# Sheet3.net
KiCad netlist of a schematic drawn in Altium Designer
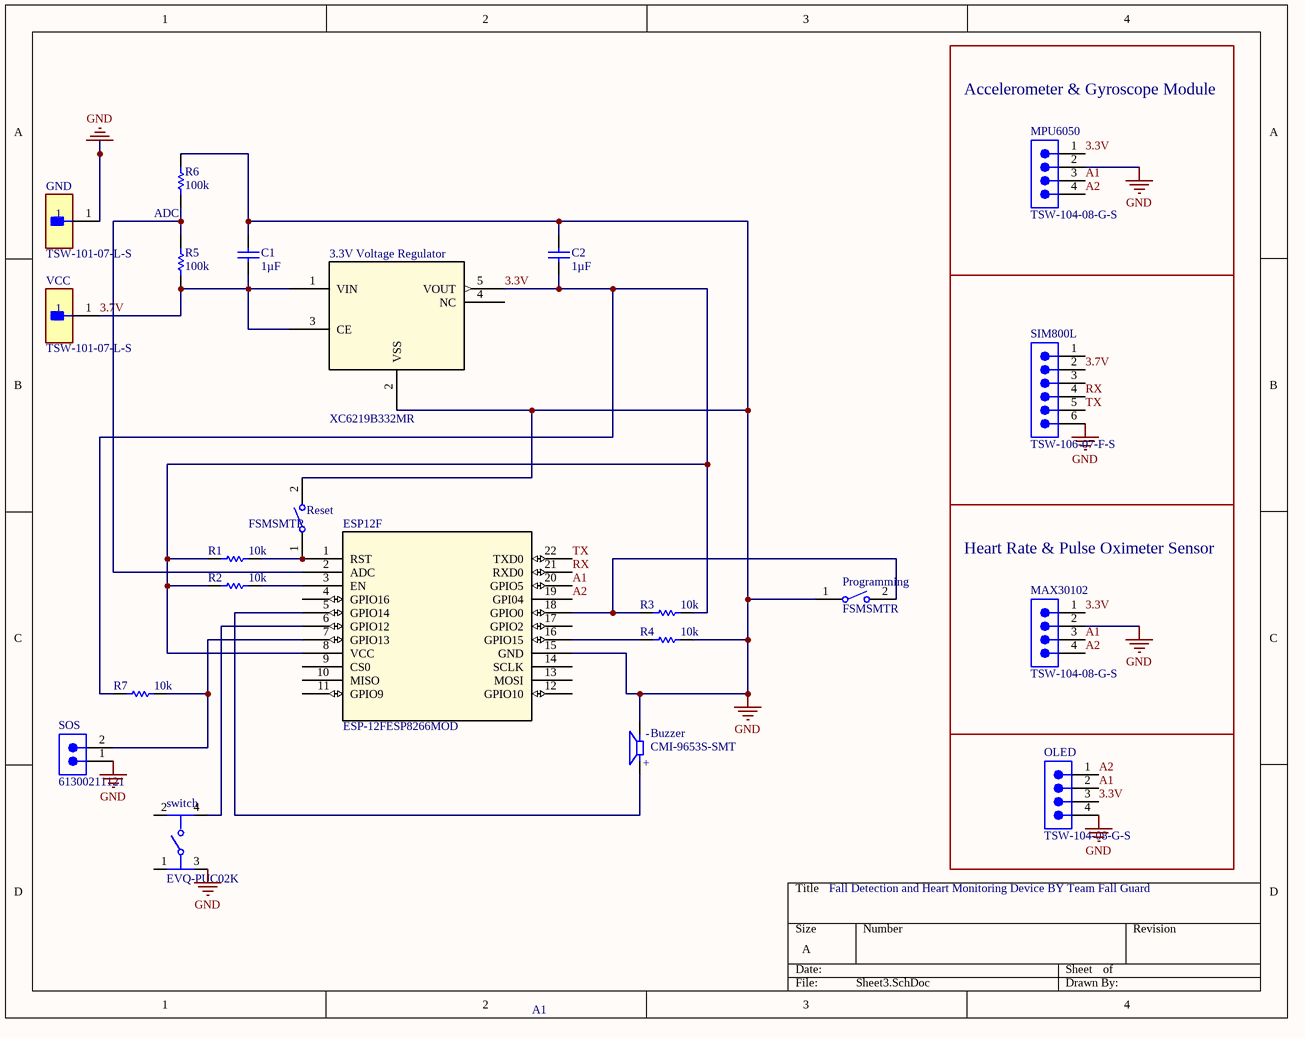
[diagram p0: Sheet3.SchDoc]

(export (version "E")
  (design (tool "Eeschema 10.0.6"))
  (components
    (comp (ref "3.3V Voltage Regulator")
      (value "XC6219B332MR")
      (footprint "SOT-25_TOR")
      (description "No Description Available")
      (libsource (lib "XC6219B332MR") (part "XC6219B332MR"))
    )
    (comp (ref "Buzzer")
      (value "CMI-9653S-SMT")
      (footprint "CUI_CMI-9653S-SMT")
      (fields (field (name "MF") "Same Sky") (field (name "MP") "CMI-9653S-SMT-TR"))
      (libsource (lib "CMI-9653S-SMT") (part "CMI-9653S-SMT"))
    )
    (comp (ref "C1")
      (value "1µF")
      (footprint "CAPC1608X90X35LL10T15")
      (description "Chip Capacitor, 1 uF, +/- 10%, 10 V, -55 to 85 degC, 0603 (1608 Metric), RoHS, Tape and Reel")
      (fields (field (name "MANUFACTURER") "Murata") (field (name "TOLERANCE") "10%"))
      (libsource (lib "Altium Content Vault") (part "CAP-NP-2"))
    )
    (comp (ref "C2")
      (value "1µF")
      (footprint "CAPC1608X90X35LL10T15")
      (description "Chip Capacitor, 1 uF, +/- 10%, 10 V, -55 to 85 degC, 0603 (1608 Metric), RoHS, Tape and Reel")
      (fields (field (name "MANUFACTURER") "Murata") (field (name "TOLERANCE") "10%"))
      (libsource (lib "Altium Content Vault") (part "CAP-NP-2"))
    )
    (comp (ref "ESP12F")
      (value "ESP-12FESP8266MOD")
      (footprint "ESP-12FESP8266MOD_AIT")
      (description "No Description Available")
      (libsource (lib "ESP-12FESP8266MOD") (part "ESP-12FESP8266MOD"))
    )
    (comp (ref "GND")
      (value "TSW-101-07-L-S")
      (footprint "FP-TSW-101-07-L-S-MFG")
      (description "CONN HEADER VERT 1POS")
      (libsource (lib "Altium Content Vault") (part "dd45045ce8184df9e99e12baf3f412c"))
    )
    (comp (ref "MAX30102")
      (value "TSW-104-08-G-S")
      (footprint "SMTC-TSW-104-08-X-S")
      (description "0.025\" SQ Post Header, Through-hole, Vertical, -55 to 125 degC, 2.54 mm Pitch, 4-Pin, Male, RoHS")
      (fields (field (name "MANUFACTURER") "Samtec"))
      (libsource (lib "Altium Content Vault") (part "SMTC-TSW-104-08-X-S"))
    )
    (comp (ref "MPU6050")
      (value "TSW-104-08-G-S")
      (footprint "SMTC-TSW-104-08-X-S")
      (description "0.025\" SQ Post Header, Through-hole, Vertical, -55 to 125 degC, 2.54 mm Pitch, 4-Pin, Male, RoHS")
      (fields (field (name "MANUFACTURER") "Samtec"))
      (libsource (lib "Altium Content Vault") (part "SMTC-TSW-104-08-X-S"))
    )
    (comp (ref "OLED")
      (value "TSW-104-08-G-S")
      (footprint "SMTC-TSW-104-08-X-S")
      (description "0.025\" SQ Post Header, Through-hole, Vertical, -55 to 125 degC, 2.54 mm Pitch, 4-Pin, Male, RoHS")
      (fields (field (name "MANUFACTURER") "Samtec"))
      (libsource (lib "Altium Content Vault") (part "SMTC-TSW-104-08-X-S"))
    )
    (comp (ref "Programming")
      (value "FSMSMTR")
      (footprint "TECO-FSMSMTR_V")
      (description "FSMSM Push Button Switch, 50 mA, -35 to 85 degC, 2-Pin SMD, RoHS, Tape and Reel")
      (fields (field (name "MANUFACTURER") "TE Connectivity"))
      (libsource (lib "Altium Content Vault") (part "SW-SPST-2_C"))
    )
    (comp (ref "R1")
      (value "10k")
      (footprint "RESC1609X50X30NL8T20")
      (description "Chip Resistor, 10 KOhm, +/- 1%, 100 mW, -55 to 155 degC, 0603 (1608 Metric), RoHS, Tape and Reel")
      (fields (field (name "MANUFACTURER") "Vishay Semiconductor"))
      (libsource (lib "Altium Content Vault") (part "RES-2"))
    )
    (comp (ref "R2")
      (value "10k")
      (footprint "RESC1609X50X30NL8T20")
      (description "Chip Resistor, 10 KOhm, +/- 1%, 100 mW, -55 to 155 degC, 0603 (1608 Metric), RoHS, Tape and Reel")
      (fields (field (name "MANUFACTURER") "Vishay Semiconductor"))
      (libsource (lib "Altium Content Vault") (part "RES-2"))
    )
    (comp (ref "R3")
      (value "10k")
      (footprint "RESC1609X50X30NL8T20")
      (description "Chip Resistor, 10 KOhm, +/- 1%, 100 mW, -55 to 155 degC, 0603 (1608 Metric), RoHS, Tape and Reel")
      (fields (field (name "MANUFACTURER") "Vishay Semiconductor"))
      (libsource (lib "Altium Content Vault") (part "RES-2"))
    )
    (comp (ref "R4")
      (value "10k")
      (footprint "RESC1609X50X30NL8T20")
      (description "Chip Resistor, 10 KOhm, +/- 1%, 100 mW, -55 to 155 degC, 0603 (1608 Metric), RoHS, Tape and Reel")
      (fields (field (name "MANUFACTURER") "Vishay Semiconductor"))
      (libsource (lib "Altium Content Vault") (part "RES-2"))
    )
    (comp (ref "R5")
      (value "100k")
      (footprint "RESC1609X50X30NL8T20")
      (description "Chip Resistor, 10 KOhm, +/- 1%, 100 mW, -55 to 155 degC, 0603 (1608 Metric), RoHS, Tape and Reel")
      (fields (field (name "MANUFACTURER") "Vishay Semiconductor"))
      (libsource (lib "Altium Content Vault") (part "RES-2"))
    )
    (comp (ref "R6")
      (value "100k")
      (footprint "RESC1609X50X30NL8T20")
      (description "Chip Resistor, 10 KOhm, +/- 1%, 100 mW, -55 to 155 degC, 0603 (1608 Metric), RoHS, Tape and Reel")
      (fields (field (name "MANUFACTURER") "Vishay Semiconductor"))
      (libsource (lib "Altium Content Vault") (part "RES-2"))
    )
    (comp (ref "R7")
      (value "10k")
      (footprint "RESC1609X50X30NL8T20")
      (description "Chip Resistor, 10 KOhm, +/- 1%, 100 mW, -55 to 155 degC, 0603 (1608 Metric), RoHS, Tape and Reel")
      (fields (field (name "MANUFACTURER") "Vishay Semiconductor"))
      (libsource (lib "Altium Content Vault") (part "RES-2"))
    )
    (comp (ref "Reset")
      (value "FSMSMTR")
      (footprint "TECO-FSMSMTR_V")
      (description "FSMSM Push Button Switch, 50 mA, -35 to 85 degC, 2-Pin SMD, RoHS, Tape and Reel")
      (fields (field (name "MANUFACTURER") "TE Connectivity"))
      (libsource (lib "Altium Content Vault") (part "SW-SPST-2_C"))
    )
    (comp (ref "SIM800L")
      (value "TSW-106-07-F-S")
      (footprint "SMTC-TSW-106-07-X-S")
      (description "0.025\" SQ Post Header, Through-hole, Vertical, -55 to 125 degC, 2.54 mm Pitch, 6-Pin, Male, RoHS")
      (fields (field (name "MANUFACTURER") "Samtec"))
      (libsource (lib "Altium Content Vault") (part "SMTC-TSW-106-X-X-S-X"))
    )
    (comp (ref "SOS")
      (value "61300211121")
      (footprint "61300211121")
      (libsource (lib "Altium Content Vault") (part "Header_Male_1R_02P"))
    )
    (comp (ref "switch")
      (value "EVQ-PUC02K")
      (footprint "FP-EVQ-PUC02K-MFG")
      (description "SWITCH TACTILE SPST-NO 0.05A 12V")
      (libsource (lib "Altium Content Vault") (part "cb67941ecbda1860b707deecc235d4d"))
    )
    (comp (ref "VCC")
      (value "TSW-101-07-L-S")
      (footprint "FP-TSW-101-07-L-S-MFG")
      (description "CONN HEADER VERT 1POS")
      (libsource (lib "Altium Content Vault") (part "dd45045ce8184df9e99e12baf3f412c"))
    )
  )
  (nets
    (net (code "1") (name "/3.3V") (class "Default")
      (node (ref "3.3V Voltage Regulator") (pin "5") (pinfunction "VOUT_5") (pintype "output"))
      (node (ref "C2") (pin "1") (pinfunction "1_1") (pintype "passive"))
      (node (ref "ESP12F") (pin "8") (pinfunction "VCC_8") (pintype "power_in"))
      (node (ref "MAX30102") (pin "1") (pinfunction "1_1") (pintype "passive"))
      (node (ref "MPU6050") (pin "1") (pinfunction "1_1") (pintype "passive"))
      (node (ref "OLED") (pin "3") (pinfunction "3_3") (pintype "passive"))
      (node (ref "R1") (pin "1") (pinfunction "1_1") (pintype "passive"))
      (node (ref "R2") (pin "1") (pinfunction "1_1") (pintype "passive"))
      (node (ref "R3") (pin "2") (pinfunction "2_2") (pintype "passive"))
      (node (ref "R7") (pin "1") (pinfunction "1_1") (pintype "passive"))
    )
    (net (code "2") (name "/3.7V") (class "Default")
      (node (ref "3.3V Voltage Regulator") (pin "1") (pinfunction "VIN_1") (pintype "power_in"))
      (node (ref "3.3V Voltage Regulator") (pin "3") (pinfunction "CE_3") (pintype "passive"))
      (node (ref "C1") (pin "1") (pinfunction "1_1") (pintype "passive"))
      (node (ref "R5") (pin "2") (pinfunction "2_2") (pintype "passive"))
      (node (ref "SIM800L") (pin "2") (pinfunction "2_2") (pintype "passive"))
      (node (ref "VCC") (pin "1") (pinfunction "1_1") (pintype "passive"))
    )
    (net (code "3") (name "/A1") (class "Default")
      (node (ref "ESP12F") (pin "20") (pinfunction "GPIO5_20") (pintype "bidirectional"))
      (node (ref "MAX30102") (pin "3") (pinfunction "3_3") (pintype "passive"))
      (node (ref "MPU6050") (pin "3") (pinfunction "3_3") (pintype "passive"))
      (node (ref "OLED") (pin "2") (pinfunction "2_2") (pintype "passive"))
    )
    (net (code "4") (name "/A2") (class "Default")
      (node (ref "ESP12F") (pin "19") (pinfunction "GPI04_19") (pintype "passive"))
      (node (ref "MAX30102") (pin "4") (pinfunction "4_4") (pintype "passive"))
      (node (ref "MPU6050") (pin "4") (pinfunction "4_4") (pintype "passive"))
      (node (ref "OLED") (pin "1") (pinfunction "1_1") (pintype "passive"))
    )
    (net (code "5") (name "/RX") (class "Default")
      (node (ref "ESP12F") (pin "21") (pinfunction "RXD0_21") (pintype "bidirectional"))
      (node (ref "SIM800L") (pin "4") (pinfunction "4_4") (pintype "passive"))
    )
    (net (code "6") (name "/TX") (class "Default")
      (node (ref "ESP12F") (pin "22") (pinfunction "TXD0_22") (pintype "bidirectional"))
      (node (ref "SIM800L") (pin "5") (pinfunction "5_5") (pintype "passive"))
    )
    (net (code "7") (name "GND") (class "Default")
      (node (ref "3.3V Voltage Regulator") (pin "2") (pinfunction "VSS_2") (pintype "power_in"))
      (node (ref "Buzzer") (pin "N") (pinfunction "N_N") (pintype "passive"))
      (node (ref "C1") (pin "2") (pinfunction "2_2") (pintype "passive"))
      (node (ref "C2") (pin "2") (pinfunction "2_2") (pintype "passive"))
      (node (ref "ESP12F") (pin "15") (pinfunction "GND_15") (pintype "power_in"))
      (node (ref "GND") (pin "1") (pinfunction "1_1") (pintype "passive"))
      (node (ref "MAX30102") (pin "2") (pinfunction "2_2") (pintype "passive"))
      (node (ref "MPU6050") (pin "2") (pinfunction "2_2") (pintype "passive"))
      (node (ref "OLED") (pin "4") (pinfunction "4_4") (pintype "passive"))
      (node (ref "Programming") (pin "1") (pinfunction "1_1") (pintype "passive"))
      (node (ref "R4") (pin "2") (pinfunction "2_2") (pintype "passive"))
      (node (ref "R6") (pin "2") (pinfunction "2_2") (pintype "passive"))
      (node (ref "Reset") (pin "2") (pinfunction "2_2") (pintype "passive"))
      (node (ref "SIM800L") (pin "6") (pinfunction "6_6") (pintype "passive"))
      (node (ref "SOS") (pin "1") (pinfunction "1_1") (pintype "passive"))
      (node (ref "switch") (pin "3") (pinfunction "3_3") (pintype "passive"))
    )
    (net (code "8") (name "Net-(ESP12F-ADC)") (class "Default")
      (node (ref "ESP12F") (pin "2") (pinfunction "ADC_2") (pintype "passive"))
      (node (ref "R5") (pin "1") (pinfunction "1_1") (pintype "passive"))
      (node (ref "R6") (pin "1") (pinfunction "1_1") (pintype "passive"))
    )
    (net (code "9") (name "Net-(ESP12F-EN)") (class "Default")
      (node (ref "ESP12F") (pin "3") (pinfunction "EN_3") (pintype "passive"))
      (node (ref "R2") (pin "2") (pinfunction "2_2") (pintype "passive"))
    )
    (net (code "10") (name "Net-(ESP12F-GPIO0)") (class "Default")
      (node (ref "ESP12F") (pin "18") (pinfunction "GPIO0_18") (pintype "bidirectional"))
      (node (ref "Programming") (pin "2") (pinfunction "2_2") (pintype "passive"))
      (node (ref "R3") (pin "1") (pinfunction "1_1") (pintype "passive"))
    )
    (net (code "11") (name "Net-(ESP12F-GPIO12)") (class "Default")
      (node (ref "ESP12F") (pin "6") (pinfunction "GPIO12_6") (pintype "bidirectional"))
      (node (ref "switch") (pin "4") (pinfunction "4_4") (pintype "passive"))
    )
    (net (code "12") (name "Net-(ESP12F-GPIO13)") (class "Default")
      (node (ref "ESP12F") (pin "7") (pinfunction "GPIO13_7") (pintype "bidirectional"))
      (node (ref "R7") (pin "2") (pinfunction "2_2") (pintype "passive"))
      (node (ref "SOS") (pin "2") (pinfunction "2_2") (pintype "passive"))
    )
    (net (code "13") (name "Net-(ESP12F-GPIO14)") (class "Default")
      (node (ref "Buzzer") (pin "P") (pinfunction "P_P") (pintype "passive"))
      (node (ref "ESP12F") (pin "5") (pinfunction "GPIO14_5") (pintype "bidirectional"))
    )
    (net (code "14") (name "Net-(ESP12F-GPIO15)") (class "Default")
      (node (ref "ESP12F") (pin "16") (pinfunction "GPIO15_16") (pintype "bidirectional"))
      (node (ref "R4") (pin "1") (pinfunction "1_1") (pintype "passive"))
    )
    (net (code "15") (name "Net-(ESP12F-RST)") (class "Default")
      (node (ref "ESP12F") (pin "1") (pinfunction "RST_1") (pintype "passive"))
      (node (ref "R1") (pin "2") (pinfunction "2_2") (pintype "passive"))
      (node (ref "Reset") (pin "1") (pinfunction "1_1") (pintype "passive"))
    )
    (net (code "16") (name "unconnected-(3.3V Voltage Regulator-NC-Pad4)") (class "Default")
      (node (ref "3.3V Voltage Regulator") (pin "4") (pinfunction "NC_4") (pintype "passive"))
    )
    (net (code "17") (name "unconnected-(ESP12F-CS0-Pad9)") (class "Default")
      (node (ref "ESP12F") (pin "9") (pinfunction "CS0_9") (pintype "passive"))
    )
    (net (code "18") (name "unconnected-(ESP12F-GPIO2-Pad17)") (class "Default")
      (node (ref "ESP12F") (pin "17") (pinfunction "GPIO2_17") (pintype "bidirectional"))
    )
    (net (code "19") (name "unconnected-(ESP12F-GPIO9-Pad11)") (class "Default")
      (node (ref "ESP12F") (pin "11") (pinfunction "GPIO9_11") (pintype "bidirectional"))
    )
    (net (code "20") (name "unconnected-(ESP12F-GPIO10-Pad12)") (class "Default")
      (node (ref "ESP12F") (pin "12") (pinfunction "GPIO10_12") (pintype "bidirectional"))
    )
    (net (code "21") (name "unconnected-(ESP12F-GPIO16-Pad4)") (class "Default")
      (node (ref "ESP12F") (pin "4") (pinfunction "GPIO16_4") (pintype "bidirectional"))
    )
    (net (code "22") (name "unconnected-(ESP12F-MISO-Pad10)") (class "Default")
      (node (ref "ESP12F") (pin "10") (pinfunction "MISO_10") (pintype "passive"))
    )
    (net (code "23") (name "unconnected-(ESP12F-MOSI-Pad13)") (class "Default")
      (node (ref "ESP12F") (pin "13") (pinfunction "MOSI_13") (pintype "passive"))
    )
    (net (code "24") (name "unconnected-(ESP12F-SCLK-Pad14)") (class "Default")
      (node (ref "ESP12F") (pin "14") (pinfunction "SCLK_14") (pintype "passive"))
    )
    (net (code "25") (name "unconnected-(SIM800L-Pad1)") (class "Default")
      (node (ref "SIM800L") (pin "1") (pinfunction "1_1") (pintype "passive"))
    )
    (net (code "26") (name "unconnected-(SIM800L-Pad3)") (class "Default")
      (node (ref "SIM800L") (pin "3") (pinfunction "3_3") (pintype "passive"))
    )
    (net (code "27") (name "unconnected-(switch-Pad1)") (class "Default")
      (node (ref "switch") (pin "1") (pinfunction "1_1") (pintype "passive"))
    )
    (net (code "28") (name "unconnected-(switch-Pad2)") (class "Default")
      (node (ref "switch") (pin "2") (pinfunction "2_2") (pintype "passive"))
    )
  )
)
